# NST_Current_alt.net
KiCad netlist of a schematic drawn in EAGLE
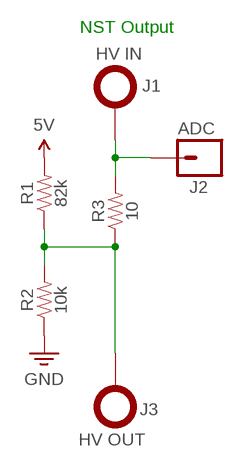
[diagram p0: schematic, sheet 1]

(export (version "E")
  (design (tool "Eeschema 10.0.6"))
  (components
    (comp (ref "J1")
      (value "HV IN")
      (footprint "eagle-import:LUG_SQUARE_M6")
      (libsource (lib "eagle-import") (part "TERMINAL_M6"))
    )
    (comp (ref "J2")
      (value "ADC")
      (footprint "eagle-import:1X01_2MM")
      (libsource (lib "eagle-import") (part "CONN_01PTH_2MM"))
    )
    (comp (ref "J3")
      (value "HV OUT")
      (footprint "eagle-import:LUG_SQUARE_M6")
      (libsource (lib "eagle-import") (part "TERMINAL_M6"))
    )
    (comp (ref "R1")
      (value "82k")
      (footprint "eagle-import:AXIAL-0.3")
      (libsource (lib "eagle-import") (part "15KOHM-HORIZ-1/4W-5%"))
    )
    (comp (ref "R2")
      (value "10k")
      (footprint "eagle-import:AXIAL-0.3")
      (libsource (lib "eagle-import") (part "15KOHM-HORIZ-1/4W-5%"))
    )
    (comp (ref "R3")
      (value "10")
      (footprint "eagle-import:AXIAL-0.3")
      (libsource (lib "eagle-import") (part "15KOHM-HORIZ-1/4W-5%"))
    )
  )
  (nets
    (net (code "1") (name "5V") (class "Default")
      (node (ref "R1") (pin "P$2") (pinfunction "2_P$2") (pintype "passive"))
    )
    (net (code "2") (name "GND") (class "Default")
      (node (ref "R2") (pin "P$1") (pinfunction "1_P$1") (pintype "passive"))
    )
    (net (code "3") (name "Net-(R1-1)") (class "Default")
      (node (ref "J3") (pin "P$1") (pinfunction "P$1_P$1") (pintype "passive"))
      (node (ref "R1") (pin "P$1") (pinfunction "1_P$1") (pintype "passive"))
      (node (ref "R2") (pin "P$2") (pinfunction "2_P$2") (pintype "passive"))
      (node (ref "R3") (pin "P$1") (pinfunction "1_P$1") (pintype "passive"))
    )
    (net (code "4") (name "Net-(R3-2)") (class "Default")
      (node (ref "J1") (pin "P$1") (pinfunction "P$1_P$1") (pintype "passive"))
      (node (ref "J2") (pin "1") (pinfunction "1_1") (pintype "passive"))
      (node (ref "R3") (pin "P$2") (pinfunction "2_P$2") (pintype "passive"))
    )
  )
)
